# ECHO.net
KiCad netlist of a schematic drawn in EAGLE
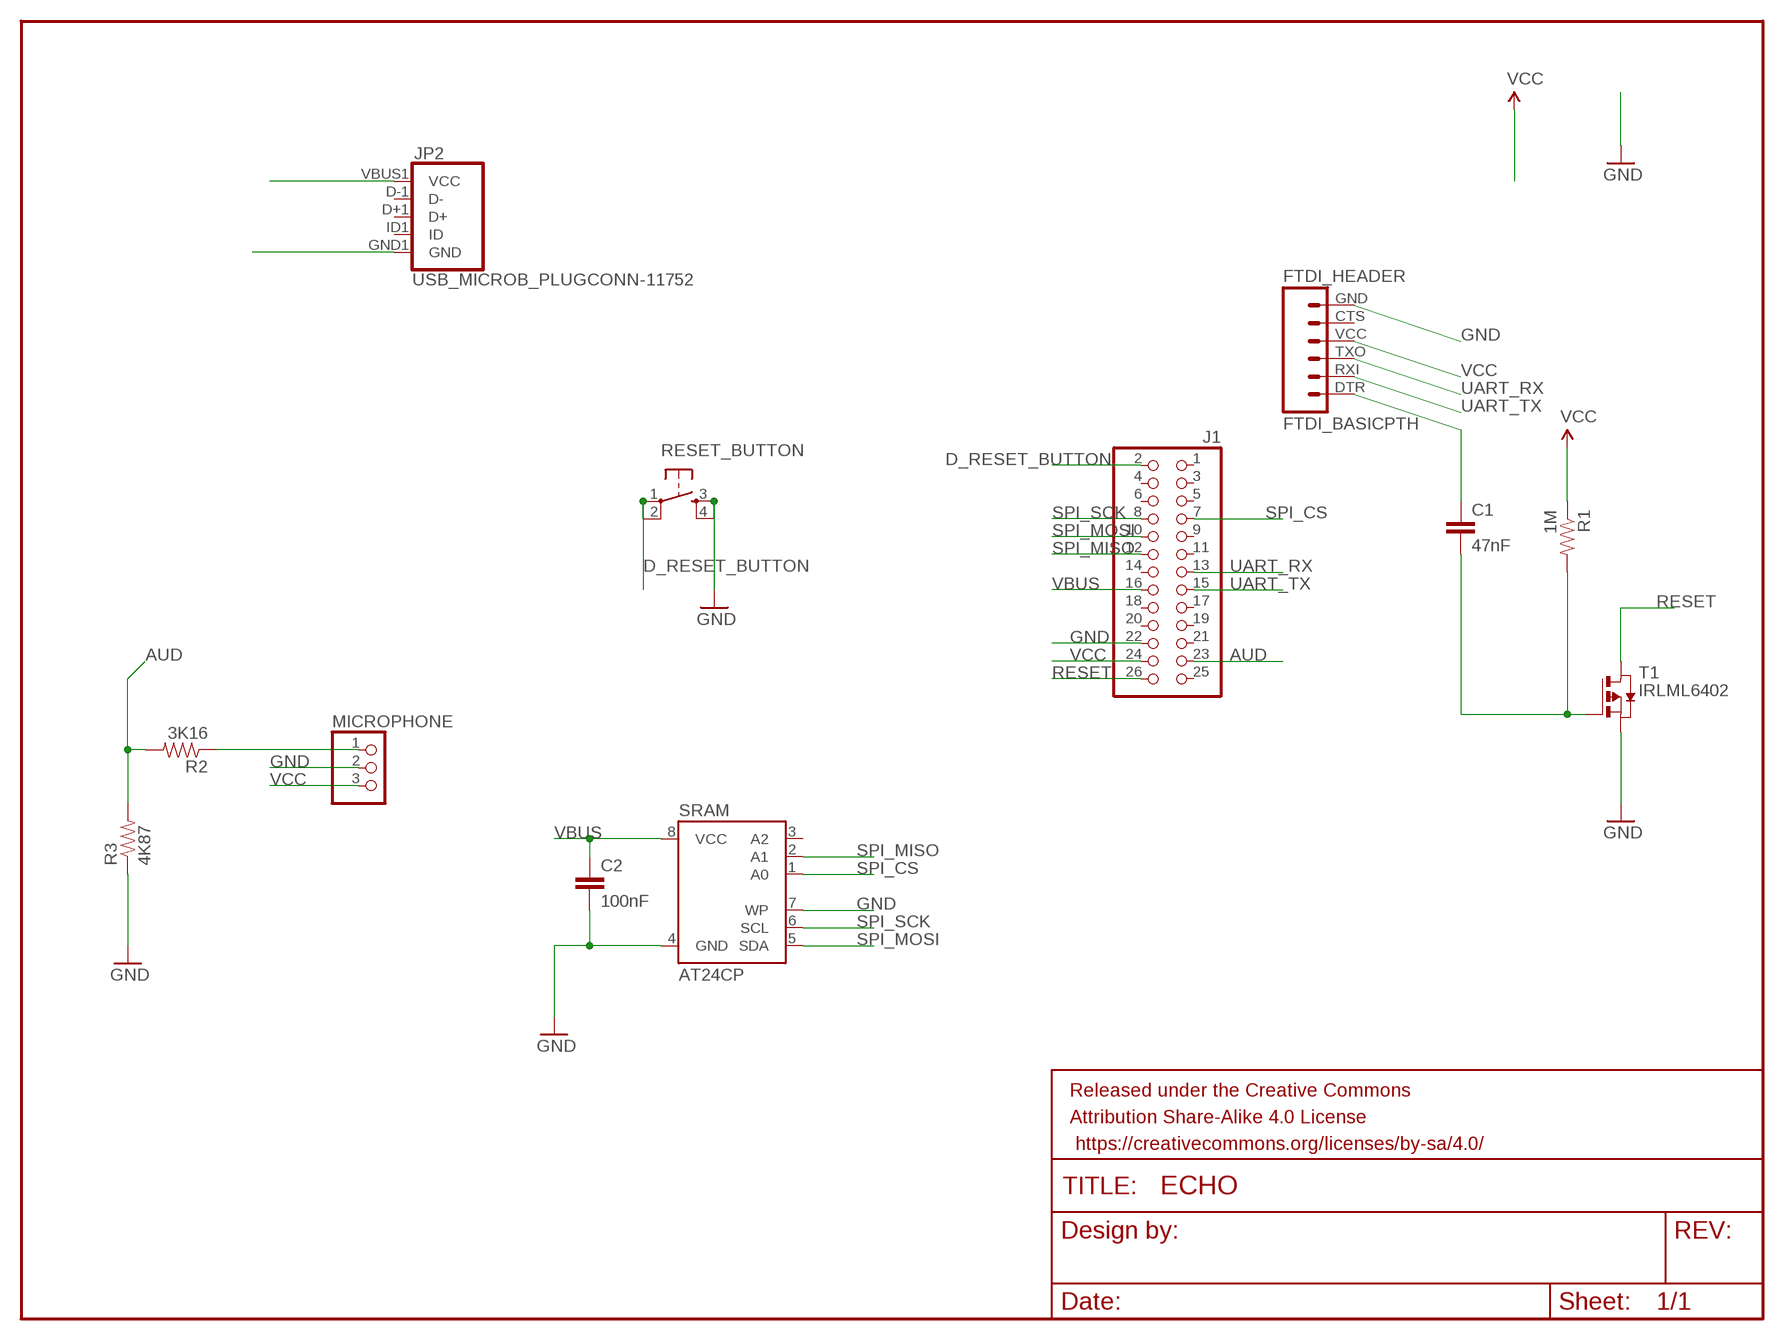
[diagram p0: schematic, sheet 1]

(export (version "E")
  (design (tool "Eeschema 10.0.6"))
  (components
    (comp (ref "C1")
      (value "47nF")
      (footprint "eagle-import:0603-CAP")
      (libsource (lib "eagle-import") (part "47NF(0.047UF/47000PF)-25V-5%(0603)SMD"))
    )
    (comp (ref "C2")
      (value "100nF")
      (footprint "eagle-import:0603-CAP")
      (libsource (lib "eagle-import") (part "10NF/10000PF-50V-10%(0603)"))
    )
    (comp (ref "FRAME1")
      (value "FRAME-LETTER")
      (footprint "eagle-import:CREATIVE_COMMONS")
      (libsource (lib "eagle-import") (part "FRAME-LETTER"))
    )
    (comp (ref "FTDI_HEADER")
      (value "FTDI_BASICPTH")
      (footprint "eagle-import:FTDI_BASIC")
      (libsource (lib "eagle-import") (part "FTDI_BASICPTH"))
    )
    (comp (ref "J1")
      (value "PINHD-2X13")
      (footprint "eagle-import:2X13")
      (libsource (lib "eagle-import") (part "PINHD-2X13"))
    )
    (comp (ref "JP2")
      (value "USB_MICROB_PLUGCONN-11752")
      (footprint "eagle-import:USB-B-MICRO-SMD_V03")
      (libsource (lib "eagle-import") (part "USB_MICROB_PLUGCONN-11752"))
    )
    (comp (ref "MICROPHONE")
      (value "PINHD-1X3")
      (footprint "eagle-import:1X03")
      (libsource (lib "eagle-import") (part "PINHD-1X3"))
    )
    (comp (ref "R1")
      (value "1M")
      (footprint "eagle-import:0603-RES")
      (libsource (lib "eagle-import") (part "1MOHM1/10W1%(0603)"))
    )
    (comp (ref "R2")
      (value "3K16")
      (footprint "eagle-import:0603-RES")
      (libsource (lib "eagle-import") (part "1OHM1/10W1%(0603)"))
    )
    (comp (ref "R3")
      (value "4K87")
      (footprint "eagle-import:0603-RES")
      (libsource (lib "eagle-import") (part "1OHM1/10W1%(0603)"))
    )
    (comp (ref "RESET_BUTTON")
      (value "TAC_SWITCHSMD")
      (footprint "eagle-import:TACTILE-SWITCH-SMD")
      (libsource (lib "eagle-import") (part "TAC_SWITCHSMD"))
    )
    (comp (ref "SRAM")
      (value "AT24CP")
      (footprint "eagle-import:DIL08")
      (fields (field (name "MPN") "AT24C1024BW-SH-B"))
      (libsource (lib "eagle-import") (part "AT24CP"))
    )
    (comp (ref "T1")
      (value "IRLML6402")
      (footprint "eagle-import:SOT-23")
      (libsource (lib "eagle-import") (part "IRLML6402"))
    )
  )
  (nets
    (net (code "1") (name "/AUD") (class "Default")
      (node (ref "J1") (pin "23") (pinfunction "23_23") (pintype "passive"))
      (node (ref "R2") (pin "2") (pinfunction "2_2") (pintype "passive"))
      (node (ref "R3") (pin "2") (pinfunction "2_2") (pintype "passive"))
    )
    (net (code "2") (name "/D_RESET_BUTTON") (class "Default")
      (node (ref "J1") (pin "2") (pinfunction "2_2") (pintype "passive"))
      (node (ref "RESET_BUTTON") (pin "1") (pinfunction "1_1") (pintype "passive"))
      (node (ref "RESET_BUTTON") (pin "2") (pinfunction "2_2") (pintype "passive"))
    )
    (net (code "3") (name "/RESET") (class "Default")
      (node (ref "J1") (pin "26") (pinfunction "26_26") (pintype "passive"))
      (node (ref "T1") (pin "3") (pinfunction "D_3") (pintype "passive"))
    )
    (net (code "4") (name "/SPI_CS") (class "Default")
      (node (ref "J1") (pin "7") (pinfunction "7_7") (pintype "passive"))
      (node (ref "SRAM") (pin "1") (pinfunction "A0_1") (pintype "input"))
    )
    (net (code "5") (name "/SPI_MISO") (class "Default")
      (node (ref "J1") (pin "12") (pinfunction "12_12") (pintype "passive"))
      (node (ref "SRAM") (pin "2") (pinfunction "A1_2") (pintype "input"))
    )
    (net (code "6") (name "/SPI_MOSI") (class "Default")
      (node (ref "J1") (pin "10") (pinfunction "10_10") (pintype "passive"))
      (node (ref "SRAM") (pin "5") (pinfunction "SDA_5") (pintype "bidirectional"))
    )
    (net (code "7") (name "/SPI_SCK") (class "Default")
      (node (ref "J1") (pin "8") (pinfunction "8_8") (pintype "passive"))
      (node (ref "SRAM") (pin "6") (pinfunction "SCL_6") (pintype "bidirectional"))
    )
    (net (code "8") (name "/UART_RX") (class "Default")
      (node (ref "FTDI_HEADER") (pin "TXO") (pinfunction "3_TXO") (pintype "passive"))
      (node (ref "J1") (pin "13") (pinfunction "13_13") (pintype "passive"))
    )
    (net (code "9") (name "/UART_TX") (class "Default")
      (node (ref "FTDI_HEADER") (pin "RXI") (pinfunction "2_RXI") (pintype "passive"))
      (node (ref "J1") (pin "15") (pinfunction "15_15") (pintype "passive"))
    )
    (net (code "10") (name "/VBUS") (class "Default")
      (node (ref "C2") (pin "1") (pinfunction "1_1") (pintype "passive"))
      (node (ref "J1") (pin "16") (pinfunction "16_16") (pintype "passive"))
      (node (ref "JP2") (pin "VBUS1") (pinfunction "VCC_VBUS1") (pintype "bidirectional"))
      (node (ref "SRAM") (pin "8") (pinfunction "VCC_8") (pintype "power_in"))
    )
    (net (code "11") (name "GND") (class "Default")
      (node (ref "C2") (pin "2") (pinfunction "2_2") (pintype "passive"))
      (node (ref "FTDI_HEADER") (pin "GND") (pinfunction "6_GND") (pintype "passive"))
      (node (ref "J1") (pin "22") (pinfunction "22_22") (pintype "passive"))
      (node (ref "JP2") (pin "GND1") (pinfunction "GND_GND1") (pintype "bidirectional"))
      (node (ref "MICROPHONE") (pin "2") (pinfunction "2_2") (pintype "passive"))
      (node (ref "R3") (pin "1") (pinfunction "1_1") (pintype "passive"))
      (node (ref "RESET_BUTTON") (pin "3") (pinfunction "3_3") (pintype "passive"))
      (node (ref "RESET_BUTTON") (pin "4") (pinfunction "4_4") (pintype "passive"))
      (node (ref "SRAM") (pin "4") (pinfunction "GND_4") (pintype "power_in"))
      (node (ref "SRAM") (pin "7") (pinfunction "WP_7") (pintype "input"))
      (node (ref "T1") (pin "2") (pinfunction "S_2") (pintype "passive"))
    )
    (net (code "12") (name "Net-(FTDI_HEADER-1)") (class "Default")
      (node (ref "C1") (pin "1") (pinfunction "1_1") (pintype "passive"))
      (node (ref "FTDI_HEADER") (pin "DTR") (pinfunction "1_DTR") (pintype "passive"))
    )
    (net (code "13") (name "Net-(MICROPHONE-Pad1)") (class "Default")
      (node (ref "MICROPHONE") (pin "1") (pinfunction "1_1") (pintype "passive"))
      (node (ref "R2") (pin "1") (pinfunction "1_1") (pintype "passive"))
    )
    (net (code "14") (name "Net-(T1-G)") (class "Default")
      (node (ref "C1") (pin "2") (pinfunction "2_2") (pintype "passive"))
      (node (ref "R1") (pin "2") (pinfunction "2_2") (pintype "passive"))
      (node (ref "T1") (pin "1") (pinfunction "G_1") (pintype "passive"))
    )
    (net (code "15") (name "VCC") (class "Default")
      (node (ref "FTDI_HEADER") (pin "VCC") (pinfunction "4_VCC") (pintype "passive"))
      (node (ref "J1") (pin "24") (pinfunction "24_24") (pintype "passive"))
      (node (ref "MICROPHONE") (pin "3") (pinfunction "3_3") (pintype "passive"))
      (node (ref "R1") (pin "1") (pinfunction "1_1") (pintype "passive"))
    )
    (net (code "16") (name "unconnected-(FTDI_HEADER-5-PadCTS)") (class "Default")
      (node (ref "FTDI_HEADER") (pin "CTS") (pinfunction "5_CTS") (pintype "passive"))
    )
    (net (code "17") (name "unconnected-(J1-Pad1)") (class "Default")
      (node (ref "J1") (pin "1") (pinfunction "1_1") (pintype "passive"))
    )
    (net (code "18") (name "unconnected-(J1-Pad3)") (class "Default")
      (node (ref "J1") (pin "3") (pinfunction "3_3") (pintype "passive"))
    )
    (net (code "19") (name "unconnected-(J1-Pad4)") (class "Default")
      (node (ref "J1") (pin "4") (pinfunction "4_4") (pintype "passive"))
    )
    (net (code "20") (name "unconnected-(J1-Pad5)") (class "Default")
      (node (ref "J1") (pin "5") (pinfunction "5_5") (pintype "passive"))
    )
    (net (code "21") (name "unconnected-(J1-Pad6)") (class "Default")
      (node (ref "J1") (pin "6") (pinfunction "6_6") (pintype "passive"))
    )
    (net (code "22") (name "unconnected-(J1-Pad9)") (class "Default")
      (node (ref "J1") (pin "9") (pinfunction "9_9") (pintype "passive"))
    )
    (net (code "23") (name "unconnected-(J1-Pad11)") (class "Default")
      (node (ref "J1") (pin "11") (pinfunction "11_11") (pintype "passive"))
    )
    (net (code "24") (name "unconnected-(J1-Pad14)") (class "Default")
      (node (ref "J1") (pin "14") (pinfunction "14_14") (pintype "passive"))
    )
    (net (code "25") (name "unconnected-(J1-Pad17)") (class "Default")
      (node (ref "J1") (pin "17") (pinfunction "17_17") (pintype "passive"))
    )
    (net (code "26") (name "unconnected-(J1-Pad18)") (class "Default")
      (node (ref "J1") (pin "18") (pinfunction "18_18") (pintype "passive"))
    )
    (net (code "27") (name "unconnected-(J1-Pad19)") (class "Default")
      (node (ref "J1") (pin "19") (pinfunction "19_19") (pintype "passive"))
    )
    (net (code "28") (name "unconnected-(J1-Pad20)") (class "Default")
      (node (ref "J1") (pin "20") (pinfunction "20_20") (pintype "passive"))
    )
    (net (code "29") (name "unconnected-(J1-Pad21)") (class "Default")
      (node (ref "J1") (pin "21") (pinfunction "21_21") (pintype "passive"))
    )
    (net (code "30") (name "unconnected-(J1-Pad25)") (class "Default")
      (node (ref "J1") (pin "25") (pinfunction "25_25") (pintype "passive"))
    )
    (net (code "31") (name "unconnected-(JP2-D+-PadD+1)") (class "Default")
      (node (ref "JP2") (pin "D+1") (pinfunction "D+_D+1") (pintype "bidirectional"))
    )
    (net (code "32") (name "unconnected-(JP2-D--PadD-1)") (class "Default")
      (node (ref "JP2") (pin "D-1") (pinfunction "D-_D-1") (pintype "bidirectional"))
    )
    (net (code "33") (name "unconnected-(JP2-ID-PadID1)") (class "Default")
      (node (ref "JP2") (pin "ID1") (pinfunction "ID_ID1") (pintype "bidirectional"))
    )
    (net (code "34") (name "unconnected-(SRAM-A2-Pad3)") (class "Default")
      (node (ref "SRAM") (pin "3") (pinfunction "A2_3") (pintype "input"))
    )
  )
)
